# Chargeur_batt.net
KiCad netlist of a schematic drawn in EAGLE
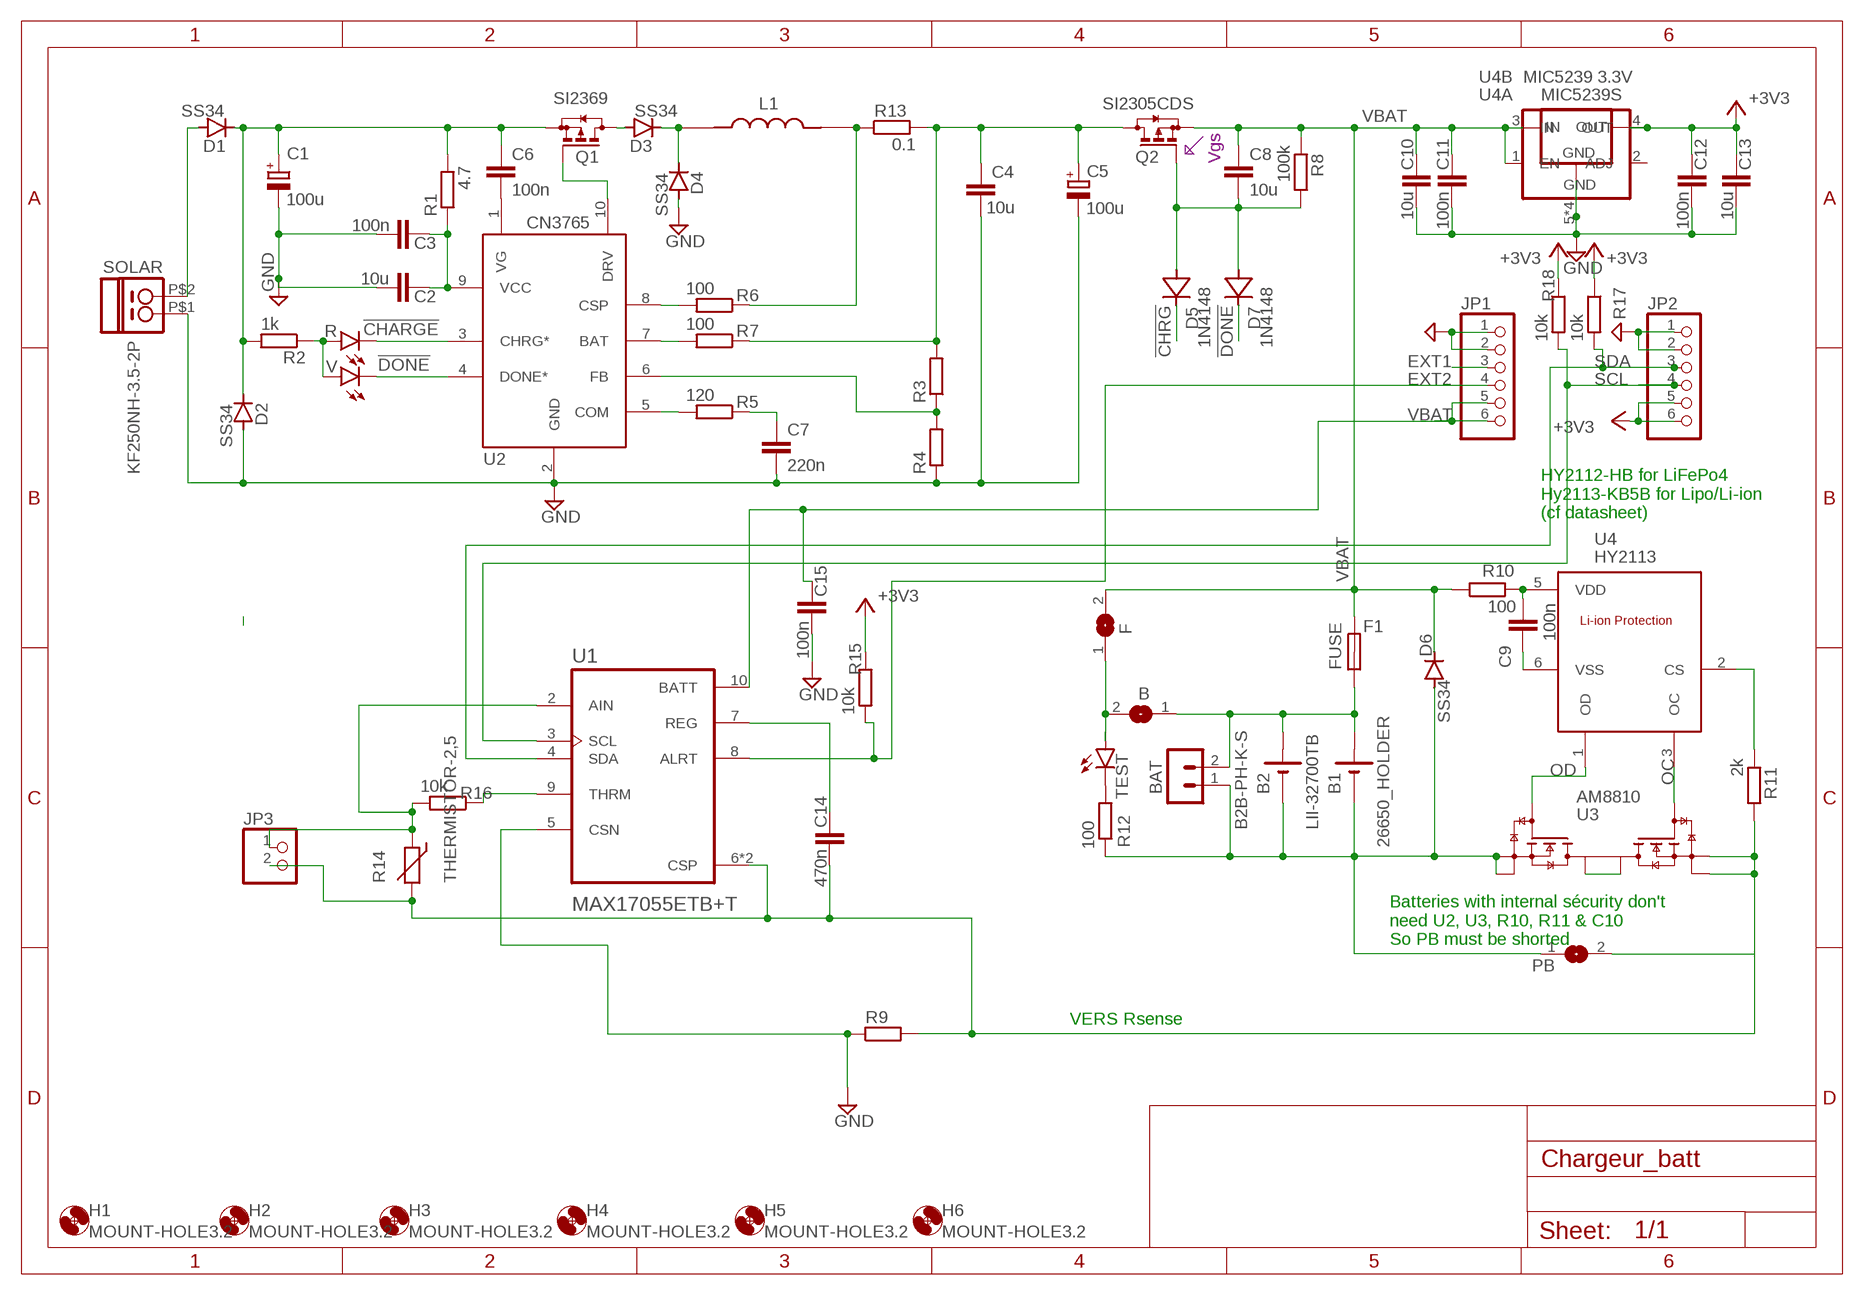
[diagram p0: schematic, sheet 1]

(export (version "E")
  (design (tool "Eeschema 10.0.6"))
  (components
    (comp (ref "B") (value "SJ") (footprint "eagle-import:SJ") (libsource (lib "eagle-import") (part "SJ")))
    (comp (ref "B1")
      (value "26650_HOLDER")
      (footprint "eagle-import:26650")
      (libsource (lib "eagle-import") (part "26650_HOLDER"))
    )
    (comp (ref "B2")
      (value "LII-32700TB")
      (footprint "eagle-import:LII-32700TB")
      (libsource (lib "eagle-import") (part "LII-32700TB"))
    )
    (comp (ref "BAT")
      (value "B2B-PH-K-S")
      (footprint "eagle-import:B2B-PH-K-S")
      (libsource (lib "eagle-import") (part "B2B-PH-K-S"))
    )
    (comp (ref "C1")
      (value "100u")
      (footprint "eagle-import:PANASONIC_D")
      (libsource (lib "eagle-import") (part "CPOL-EUD"))
    )
    (comp (ref "C2")
      (value "10u")
      (footprint "eagle-import:C0805K")
      (libsource (lib "eagle-import") (part "C-EUC0805K"))
    )
    (comp (ref "C3")
      (value "100n")
      (footprint "eagle-import:C0805K")
      (libsource (lib "eagle-import") (part "C-EUC0805K"))
    )
    (comp (ref "C4")
      (value "10u")
      (footprint "eagle-import:C0805K")
      (libsource (lib "eagle-import") (part "C-EUC0805K"))
    )
    (comp (ref "C5")
      (value "100u")
      (footprint "eagle-import:PANASONIC_D")
      (libsource (lib "eagle-import") (part "CPOL-EUD"))
    )
    (comp (ref "C6")
      (value "100n")
      (footprint "eagle-import:C0805K")
      (libsource (lib "eagle-import") (part "C-EUC0805K"))
    )
    (comp (ref "C7")
      (value "220n")
      (footprint "eagle-import:C0805K")
      (libsource (lib "eagle-import") (part "C-EUC0805K"))
    )
    (comp (ref "C8")
      (value "10u")
      (footprint "eagle-import:C0805K")
      (libsource (lib "eagle-import") (part "C-EUC0805K"))
    )
    (comp (ref "C9")
      (value "100n")
      (footprint "eagle-import:C0805K")
      (libsource (lib "eagle-import") (part "C-EUC0805K"))
    )
    (comp (ref "C10")
      (value "10u")
      (footprint "eagle-import:C1206")
      (libsource (lib "eagle-import") (part "CC1206"))
    )
    (comp (ref "C11")
      (value "100n")
      (footprint "eagle-import:C1206")
      (libsource (lib "eagle-import") (part "CC1206"))
    )
    (comp (ref "C12")
      (value "100n")
      (footprint "eagle-import:C1206")
      (libsource (lib "eagle-import") (part "CC1206"))
    )
    (comp (ref "C13")
      (value "10u")
      (footprint "eagle-import:C1206")
      (libsource (lib "eagle-import") (part "CC1206"))
    )
    (comp (ref "C14")
      (value "470n")
      (footprint "eagle-import:C1206")
      (libsource (lib "eagle-import") (part "CC1206"))
    )
    (comp (ref "C15")
      (value "100n")
      (footprint "eagle-import:C0805K")
      (libsource (lib "eagle-import") (part "C-EUC0805K"))
    )
    (comp (ref "D1")
      (value "SS34")
      (footprint "eagle-import:DO-214AC")
      (libsource (lib "eagle-import") (part "DIODE-DO-214AC"))
    )
    (comp (ref "D2")
      (value "SS34")
      (footprint "eagle-import:DO-214AC")
      (libsource (lib "eagle-import") (part "DIODE-DO-214AC"))
    )
    (comp (ref "D3")
      (value "SS34")
      (footprint "eagle-import:DO-214AC")
      (libsource (lib "eagle-import") (part "DIODE-DO-214AC"))
    )
    (comp (ref "D4")
      (value "SS34")
      (footprint "eagle-import:DO-214AC")
      (libsource (lib "eagle-import") (part "DIODE-DO-214AC"))
    )
    (comp (ref "D5")
      (value "1N4148")
      (footprint "eagle-import:VISHAY_1N4148W-E3-08_0")
      (libsource (lib "eagle-import") (part "1N4148"))
    )
    (comp (ref "D6")
      (value "SS34")
      (footprint "eagle-import:DO-214AC")
      (libsource (lib "eagle-import") (part "DIODE-DO-214AC"))
    )
    (comp (ref "D7")
      (value "1N4148")
      (footprint "eagle-import:VISHAY_1N4148W-E3-08_0")
      (libsource (lib "eagle-import") (part "1N4148"))
    )
    (comp (ref "F") (value "SJ") (footprint "eagle-import:SJ") (libsource (lib "eagle-import") (part "SJ")))
    (comp (ref "F1")
      (value "FUSE")
      (footprint "eagle-import:R1206")
      (libsource (lib "eagle-import") (part "FUSE"))
    )
    (comp (ref "H1")
      (value "MOUNT-HOLE3.2")
      (footprint "eagle-import:3,2")
      (libsource (lib "eagle-import") (part "MOUNT-HOLE3.2"))
    )
    (comp (ref "H2")
      (value "MOUNT-HOLE3.2")
      (footprint "eagle-import:3,2")
      (libsource (lib "eagle-import") (part "MOUNT-HOLE3.2"))
    )
    (comp (ref "H3")
      (value "MOUNT-HOLE3.2")
      (footprint "eagle-import:3,2")
      (libsource (lib "eagle-import") (part "MOUNT-HOLE3.2"))
    )
    (comp (ref "H4")
      (value "MOUNT-HOLE3.2")
      (footprint "eagle-import:3,2")
      (libsource (lib "eagle-import") (part "MOUNT-HOLE3.2"))
    )
    (comp (ref "H5")
      (value "MOUNT-HOLE3.2")
      (footprint "eagle-import:3,2")
      (libsource (lib "eagle-import") (part "MOUNT-HOLE3.2"))
    )
    (comp (ref "H6")
      (value "MOUNT-HOLE3.2")
      (footprint "eagle-import:3,2")
      (libsource (lib "eagle-import") (part "MOUNT-HOLE3.2"))
    )
    (comp (ref "JP1")
      (value "PINHD-1X6S")
      (footprint "eagle-import:1X06S")
      (libsource (lib "eagle-import") (part "PINHD-1X6S"))
    )
    (comp (ref "JP2")
      (value "PINHD-1X6S")
      (footprint "eagle-import:1X06S")
      (libsource (lib "eagle-import") (part "PINHD-1X6S"))
    )
    (comp (ref "JP3")
      (value "PINHD-1X2")
      (footprint "eagle-import:1X02")
      (libsource (lib "eagle-import") (part "PINHD-1X2"))
    )
    (comp (ref "L1")
      (value "IND15")
      (footprint "eagle-import:IND_15")
      (libsource (lib "eagle-import") (part "IND15"))
    )
    (comp (ref "PB") (value "SJ") (footprint "eagle-import:SJ") (libsource (lib "eagle-import") (part "SJ")))
    (comp (ref "Q1")
      (value "SI2369")
      (footprint "eagle-import:SOT23")
      (libsource (lib "eagle-import") (part "SI2369"))
    )
    (comp (ref "Q2")
      (value "SI2305CDS")
      (footprint "eagle-import:SOT23")
      (libsource (lib "eagle-import") (part "SI2305CDS"))
    )
    (comp (ref "R")
      (value "LEDSML0805")
      (footprint "eagle-import:SML0805")
      (libsource (lib "eagle-import") (part "LEDSML0805"))
    )
    (comp (ref "R1")
      (value "4.7")
      (footprint "eagle-import:R1206")
      (libsource (lib "eagle-import") (part "R-EU_R1206"))
    )
    (comp (ref "R2")
      (value "1k")
      (footprint "eagle-import:R1206")
      (libsource (lib "eagle-import") (part "R-EU_R1206"))
    )
    (comp (ref "R3")
      (value "R-EU_R1206")
      (footprint "eagle-import:R1206")
      (libsource (lib "eagle-import") (part "R-EU_R1206"))
    )
    (comp (ref "R4")
      (value "R-EU_R1206")
      (footprint "eagle-import:R1206")
      (libsource (lib "eagle-import") (part "R-EU_R1206"))
    )
    (comp (ref "R5")
      (value "120")
      (footprint "eagle-import:R1206")
      (libsource (lib "eagle-import") (part "R-EU_R1206"))
    )
    (comp (ref "R6")
      (value "100")
      (footprint "eagle-import:R1206")
      (libsource (lib "eagle-import") (part "R-EU_R1206"))
    )
    (comp (ref "R7")
      (value "100")
      (footprint "eagle-import:R1206")
      (libsource (lib "eagle-import") (part "R-EU_R1206"))
    )
    (comp (ref "R8")
      (value "100k")
      (footprint "eagle-import:M1206")
      (libsource (lib "eagle-import") (part "resistor_R-EU_M1206"))
    )
    (comp (ref "R9")
      (value "R-EU_R2512")
      (footprint "eagle-import:R2512")
      (libsource (lib "eagle-import") (part "R-EU_R2512"))
    )
    (comp (ref "R10")
      (value "100")
      (footprint "eagle-import:R1206")
      (libsource (lib "eagle-import") (part "R-EU_R1206"))
    )
    (comp (ref "R11")
      (value "2k")
      (footprint "eagle-import:R1206")
      (libsource (lib "eagle-import") (part "resistor_R-EU_R1206"))
    )
    (comp (ref "R12")
      (value "100")
      (footprint "eagle-import:R1206")
      (libsource (lib "eagle-import") (part "R-EU_R1206"))
    )
    (comp (ref "R13")
      (value "0.1")
      (footprint "eagle-import:R2512")
      (libsource (lib "eagle-import") (part "R-EU_R2512"))
    )
    (comp (ref "R14")
      (value "THERMISTOR-2,5")
      (footprint "eagle-import:RS-2,5")
      (libsource (lib "eagle-import") (part "THERMISTOR-2,5"))
    )
    (comp (ref "R15")
      (value "10k")
      (footprint "eagle-import:R1206")
      (libsource (lib "eagle-import") (part "R-EU_R1206"))
    )
    (comp (ref "R16")
      (value "10k")
      (footprint "eagle-import:R1206")
      (libsource (lib "eagle-import") (part "R-EU_R1206"))
    )
    (comp (ref "R17")
      (value "10k")
      (footprint "eagle-import:R1206")
      (libsource (lib "eagle-import") (part "R-EU_R1206"))
    )
    (comp (ref "R18")
      (value "10k")
      (footprint "eagle-import:R1206")
      (libsource (lib "eagle-import") (part "R-EU_R1206"))
    )
    (comp (ref "SOLAR")
      (value "KF250NH-3.5-2P")
      (footprint "eagle-import:KF250NH-3.5-2P")
      (libsource (lib "eagle-import") (part "KF250NH-3.5-2P"))
    )
    (comp (ref "TEST")
      (value "LEDSML0805")
      (footprint "eagle-import:SML0805")
      (libsource (lib "eagle-import") (part "LEDSML0805"))
    )
    (comp (ref "U1")
      (value "MAX17055ETB+T")
      (footprint "eagle-import:SON40P200X250X80-11N")
      (fields (field (name "MF") "Maxim Integrated"))
      (libsource (lib "eagle-import") (part "MAX17055ETB+T"))
    )
    (comp (ref "U2")
      (value "CN3765")
      (footprint "eagle-import:SSOP")
      (libsource (lib "eagle-import") (part "CN3765"))
    )
    (comp (ref "U3")
      (value "AM8810")
      (footprint "eagle-import:TSSOP8")
      (libsource (lib "eagle-import") (part "AM8810"))
    )
    (comp (ref "U4")
      (value "HY2113")
      (footprint "eagle-import:SOT23-6")
      (libsource (lib "eagle-import") (part "HY2113"))
    )
    (comp (ref "U4A")
      (value "MIC5239S")
      (footprint "eagle-import:SOT223")
      (libsource (lib "eagle-import") (part "MIC5239S"))
    )
    (comp (ref "U4B")
      (value "MIC5239 3.3V")
      (footprint "eagle-import:MSOP08")
      (libsource (lib "eagle-import") (part "MIC5239-ADJMM"))
    )
    (comp (ref "V")
      (value "LEDSML0805")
      (footprint "eagle-import:SML0805")
      (libsource (lib "eagle-import") (part "LEDSML0805"))
    )
  )
  (nets
    (net (code "1") (name "+3V3") (class "Default")
      (node (ref "C12") (pin "1") (pinfunction "1_1") (pintype "passive"))
      (node (ref "C13") (pin "1") (pinfunction "1_1") (pintype "passive"))
      (node (ref "JP2") (pin "5") (pinfunction "5_5") (pintype "passive"))
      (node (ref "JP2") (pin "6") (pinfunction "6_6") (pintype "passive"))
      (node (ref "R15") (pin "1") (pinfunction "1_1") (pintype "passive"))
      (node (ref "R17") (pin "1") (pinfunction "1_1") (pintype "passive"))
      (node (ref "R18") (pin "1") (pinfunction "1_1") (pintype "passive"))
      (node (ref "U4A") (pin "3") (pinfunction "OUT_3") (pintype "passive"))
      (node (ref "U4B") (pin "4") (pinfunction "OUT_4") (pintype "passive"))
    )
    (net (code "2") (name "/EXT1") (class "Default")
      (node (ref "JP1") (pin "3") (pinfunction "3_3") (pintype "passive"))
    )
    (net (code "3") (name "/EXT2") (class "Default")
      (node (ref "JP1") (pin "4") (pinfunction "4_4") (pintype "passive"))
      (node (ref "R15") (pin "2") (pinfunction "2_2") (pintype "passive"))
      (node (ref "U1") (pin "8") (pinfunction "ALRT_8") (pintype "output"))
    )
    (net (code "4") (name "/OC") (class "Default")
      (node (ref "U3") (pin "5") (pinfunction "G2_5") (pintype "passive"))
      (node (ref "U4") (pin "3") (pinfunction "OC_3") (pintype "bidirectional"))
    )
    (net (code "5") (name "/OD") (class "Default")
      (node (ref "U3") (pin "4") (pinfunction "G1_4") (pintype "passive"))
      (node (ref "U4") (pin "1") (pinfunction "OD_1") (pintype "bidirectional"))
    )
    (net (code "6") (name "/SCL") (class "Default")
      (node (ref "JP2") (pin "4") (pinfunction "4_4") (pintype "passive"))
      (node (ref "R18") (pin "2") (pinfunction "2_2") (pintype "passive"))
      (node (ref "U1") (pin "3") (pinfunction "SCL_3") (pintype "input"))
    )
    (net (code "7") (name "/SDA") (class "Default")
      (node (ref "JP2") (pin "3") (pinfunction "3_3") (pintype "passive"))
      (node (ref "R17") (pin "2") (pinfunction "2_2") (pintype "passive"))
      (node (ref "U1") (pin "4") (pinfunction "SDA_4") (pintype "input"))
    )
    (net (code "8") (name "/VBAT") (class "Default")
      (node (ref "C10") (pin "1") (pinfunction "1_1") (pintype "passive"))
      (node (ref "C11") (pin "1") (pinfunction "1_1") (pintype "passive"))
      (node (ref "C15") (pin "1") (pinfunction "1_1") (pintype "passive"))
      (node (ref "C8") (pin "1") (pinfunction "1_1") (pintype "passive"))
      (node (ref "D6") (pin "C") (pinfunction "C_C") (pintype "passive"))
      (node (ref "F") (pin "2") (pinfunction "2_2") (pintype "passive"))
      (node (ref "F1") (pin "2") (pinfunction "2_2") (pintype "passive"))
      (node (ref "JP1") (pin "5") (pinfunction "5_5") (pintype "passive"))
      (node (ref "JP1") (pin "6") (pinfunction "6_6") (pintype "passive"))
      (node (ref "Q2") (pin "2") (pinfunction "S_2") (pintype "passive"))
      (node (ref "R10") (pin "1") (pinfunction "1_1") (pintype "passive"))
      (node (ref "R8") (pin "1") (pinfunction "1_1") (pintype "passive"))
      (node (ref "U1") (pin "10") (pinfunction "BATT_10") (pintype "power_in"))
      (node (ref "U4A") (pin "1") (pinfunction "IN_1") (pintype "input"))
      (node (ref "U4B") (pin "1") (pinfunction "EN_1") (pintype "input"))
      (node (ref "U4B") (pin "3") (pinfunction "IN_3") (pintype "input"))
    )
    (net (code "9") (name "/~{CHARGE}") (class "Default")
      (node (ref "R") (pin "C") (pinfunction "C_C") (pintype "passive"))
      (node (ref "U2") (pin "3") (pinfunction "CHRG*_3") (pintype "input"))
    )
    (net (code "10") (name "/~{CHRG}") (class "Default")
      (node (ref "D5") (pin "1") (pinfunction "C_1") (pintype "passive"))
    )
    (net (code "11") (name "/~{DONE}") (class "Default")
      (node (ref "D7") (pin "1") (pinfunction "C_1") (pintype "passive"))
      (node (ref "U2") (pin "4") (pinfunction "DONE*_4") (pintype "input"))
      (node (ref "V") (pin "C") (pinfunction "C_C") (pintype "passive"))
    )
    (net (code "12") (name "GND") (class "Default")
      (node (ref "C1") (pin "-") (pinfunction "-_-") (pintype "passive"))
      (node (ref "C10") (pin "2") (pinfunction "2_2") (pintype "passive"))
      (node (ref "C11") (pin "2") (pinfunction "2_2") (pintype "passive"))
      (node (ref "C12") (pin "2") (pinfunction "2_2") (pintype "passive"))
      (node (ref "C13") (pin "2") (pinfunction "2_2") (pintype "passive"))
      (node (ref "C15") (pin "2") (pinfunction "2_2") (pintype "passive"))
      (node (ref "C2") (pin "2") (pinfunction "2_2") (pintype "passive"))
      (node (ref "C3") (pin "2") (pinfunction "2_2") (pintype "passive"))
      (node (ref "C4") (pin "2") (pinfunction "2_2") (pintype "passive"))
      (node (ref "C5") (pin "-") (pinfunction "-_-") (pintype "passive"))
      (node (ref "C7") (pin "2") (pinfunction "2_2") (pintype "passive"))
      (node (ref "D2") (pin "A") (pinfunction "A_A") (pintype "passive"))
      (node (ref "D4") (pin "A") (pinfunction "A_A") (pintype "passive"))
      (node (ref "JP1") (pin "1") (pinfunction "1_1") (pintype "passive"))
      (node (ref "JP1") (pin "2") (pinfunction "2_2") (pintype "passive"))
      (node (ref "JP2") (pin "1") (pinfunction "1_1") (pintype "passive"))
      (node (ref "JP2") (pin "2") (pinfunction "2_2") (pintype "passive"))
      (node (ref "R4") (pin "1") (pinfunction "1_1") (pintype "passive"))
      (node (ref "R9") (pin "1") (pinfunction "1_1") (pintype "passive"))
      (node (ref "SOLAR") (pin "P$1") (pinfunction "1_P$1") (pintype "passive"))
      (node (ref "U1") (pin "5") (pinfunction "CSN_5") (pintype "bidirectional"))
      (node (ref "U2") (pin "2") (pinfunction "GND_2") (pintype "power_in"))
      (node (ref "U4A") (pin "2") (pinfunction "GND_2") (pintype "passive"))
      (node (ref "U4A") (pin "4") (pinfunction "GND_4") (pintype "passive"))
      (node (ref "U4B") (pin "5") (pinfunction "GND_5") (pintype "power_in"))
      (node (ref "U4B") (pin "6") (pinfunction "GND_6") (pintype "power_in"))
      (node (ref "U4B") (pin "7") (pinfunction "GND_7") (pintype "power_in"))
      (node (ref "U4B") (pin "8") (pinfunction "GND_8") (pintype "power_in"))
    )
    (net (code "13") (name "Net-(B-Pad1)") (class "Default")
      (node (ref "B") (pin "1") (pinfunction "1_1") (pintype "passive"))
      (node (ref "B1") (pin "+") (pinfunction "+_+") (pintype "passive"))
      (node (ref "B2") (pin "+") (pinfunction "+_+") (pintype "passive"))
      (node (ref "BAT") (pin "2") (pinfunction "2_2") (pintype "passive"))
      (node (ref "F1") (pin "1") (pinfunction "1_1") (pintype "passive"))
    )
    (net (code "14") (name "Net-(B-Pad2)") (class "Default")
      (node (ref "B") (pin "2") (pinfunction "2_2") (pintype "passive"))
      (node (ref "F") (pin "1") (pinfunction "1_1") (pintype "passive"))
      (node (ref "TEST") (pin "A") (pinfunction "A_A") (pintype "passive"))
    )
    (net (code "15") (name "Net-(C7-Pad1)") (class "Default")
      (node (ref "C7") (pin "1") (pinfunction "1_1") (pintype "passive"))
      (node (ref "R5") (pin "1") (pinfunction "1_1") (pintype "passive"))
    )
    (net (code "16") (name "Net-(D3-PadC)") (class "Default")
      (node (ref "D3") (pin "C") (pinfunction "C_C") (pintype "passive"))
      (node (ref "D4") (pin "C") (pinfunction "C_C") (pintype "passive"))
      (node (ref "L1") (pin "1") (pinfunction "1_1") (pintype "passive"))
    )
    (net (code "17") (name "Net-(D5-A)") (class "Default")
      (node (ref "C8") (pin "2") (pinfunction "2_2") (pintype "passive"))
      (node (ref "D5") (pin "2") (pinfunction "A_2") (pintype "passive"))
      (node (ref "D7") (pin "2") (pinfunction "A_2") (pintype "passive"))
      (node (ref "Q2") (pin "1") (pinfunction "G_1") (pintype "passive"))
      (node (ref "R8") (pin "2") (pinfunction "2_2") (pintype "passive"))
    )
    (net (code "18") (name "Net-(L1-Pad2)") (class "Default")
      (node (ref "L1") (pin "2") (pinfunction "2_2") (pintype "passive"))
      (node (ref "R13") (pin "1") (pinfunction "1_1") (pintype "passive"))
      (node (ref "R6") (pin "1") (pinfunction "1_1") (pintype "passive"))
    )
    (net (code "19") (name "Net-(Q1-D)") (class "Default")
      (node (ref "D3") (pin "A") (pinfunction "A_A") (pintype "passive"))
      (node (ref "Q1") (pin "3") (pinfunction "D_3") (pintype "passive"))
    )
    (net (code "20") (name "Net-(Q1-G)") (class "Default")
      (node (ref "Q1") (pin "1") (pinfunction "G_1") (pintype "passive"))
      (node (ref "U2") (pin "10") (pinfunction "DRV_10") (pintype "bidirectional"))
    )
    (net (code "21") (name "Net-(Q1-S)") (class "Default")
      (node (ref "C1") (pin "+") (pinfunction "+_+") (pintype "passive"))
      (node (ref "C6") (pin "1") (pinfunction "1_1") (pintype "passive"))
      (node (ref "D1") (pin "C") (pinfunction "C_C") (pintype "passive"))
      (node (ref "D2") (pin "C") (pinfunction "C_C") (pintype "passive"))
      (node (ref "Q1") (pin "2") (pinfunction "S_2") (pintype "passive"))
      (node (ref "R1") (pin "2") (pinfunction "2_2") (pintype "passive"))
      (node (ref "R2") (pin "2") (pinfunction "2_2") (pintype "passive"))
    )
    (net (code "22") (name "Net-(Q2-D)") (class "Default")
      (node (ref "C4") (pin "1") (pinfunction "1_1") (pintype "passive"))
      (node (ref "C5") (pin "+") (pinfunction "+_+") (pintype "passive"))
      (node (ref "Q2") (pin "3") (pinfunction "D_3") (pintype "passive"))
      (node (ref "R13") (pin "2") (pinfunction "2_2") (pintype "passive"))
      (node (ref "R3") (pin "2") (pinfunction "2_2") (pintype "passive"))
      (node (ref "R7") (pin "1") (pinfunction "1_1") (pintype "passive"))
    )
    (net (code "23") (name "Net-(R-PadA)") (class "Default")
      (node (ref "R") (pin "A") (pinfunction "A_A") (pintype "passive"))
      (node (ref "R2") (pin "1") (pinfunction "1_1") (pintype "passive"))
      (node (ref "V") (pin "A") (pinfunction "A_A") (pintype "passive"))
    )
    (net (code "24") (name "Net-(R12-Pad1)") (class "Default")
      (node (ref "R12") (pin "1") (pinfunction "1_1") (pintype "passive"))
      (node (ref "TEST") (pin "C") (pinfunction "C_C") (pintype "passive"))
    )
    (net (code "25") (name "Net-(SOLAR-2)") (class "Default")
      (node (ref "D1") (pin "A") (pinfunction "A_A") (pintype "passive"))
      (node (ref "SOLAR") (pin "P$2") (pinfunction "2_P$2") (pintype "passive"))
    )
    (net (code "26") (name "Net-(U1-AIN)") (class "Default")
      (node (ref "JP3") (pin "1") (pinfunction "1_1") (pintype "passive"))
      (node (ref "R14") (pin "1") (pinfunction "1_1") (pintype "passive"))
      (node (ref "R16") (pin "2") (pinfunction "2_2") (pintype "passive"))
      (node (ref "U1") (pin "2") (pinfunction "AIN_2") (pintype "input"))
    )
    (net (code "27") (name "Net-(U1-REG)") (class "Default")
      (node (ref "C14") (pin "1") (pinfunction "1_1") (pintype "passive"))
      (node (ref "U1") (pin "7") (pinfunction "REG_7") (pintype "output"))
    )
    (net (code "28") (name "Net-(U1-THRM)") (class "Default")
      (node (ref "R16") (pin "1") (pinfunction "1_1") (pintype "passive"))
      (node (ref "U1") (pin "9") (pinfunction "THRM_9") (pintype "input"))
    )
    (net (code "29") (name "Net-(U2-BAT)") (class "Default")
      (node (ref "R7") (pin "2") (pinfunction "2_2") (pintype "passive"))
      (node (ref "U2") (pin "7") (pinfunction "BAT_7") (pintype "bidirectional"))
    )
    (net (code "30") (name "Net-(U2-COM)") (class "Default")
      (node (ref "R5") (pin "2") (pinfunction "2_2") (pintype "passive"))
      (node (ref "U2") (pin "5") (pinfunction "COM_5") (pintype "input"))
    )
    (net (code "31") (name "Net-(U2-CSP)") (class "Default")
      (node (ref "R6") (pin "2") (pinfunction "2_2") (pintype "passive"))
      (node (ref "U2") (pin "8") (pinfunction "CSP_8") (pintype "bidirectional"))
    )
    (net (code "32") (name "Net-(U2-FB)") (class "Default")
      (node (ref "R3") (pin "1") (pinfunction "1_1") (pintype "passive"))
      (node (ref "R4") (pin "2") (pinfunction "2_2") (pintype "passive"))
      (node (ref "U2") (pin "6") (pinfunction "FB_6") (pintype "input"))
    )
    (net (code "33") (name "Net-(U2-VCC)") (class "Default")
      (node (ref "C2") (pin "1") (pinfunction "1_1") (pintype "passive"))
      (node (ref "C3") (pin "1") (pinfunction "1_1") (pintype "passive"))
      (node (ref "R1") (pin "1") (pinfunction "1_1") (pintype "passive"))
      (node (ref "U2") (pin "9") (pinfunction "VCC_9") (pintype "power_in"))
    )
    (net (code "34") (name "Net-(U2-VG)") (class "Default")
      (node (ref "C6") (pin "2") (pinfunction "2_2") (pintype "passive"))
      (node (ref "U2") (pin "1") (pinfunction "VG_1") (pintype "bidirectional"))
    )
    (net (code "35") (name "Net-(U3-D1)") (class "Default")
      (node (ref "U3") (pin "1") (pinfunction "D1_1") (pintype "passive"))
      (node (ref "U3") (pin "8") (pinfunction "D2_8") (pintype "passive"))
    )
    (net (code "36") (name "Net-(U3-S1)") (class "Default")
      (node (ref "B1") (pin "-") (pinfunction "-_-") (pintype "passive"))
      (node (ref "B2") (pin "-") (pinfunction "-_-") (pintype "passive"))
      (node (ref "BAT") (pin "1") (pinfunction "1_1") (pintype "passive"))
      (node (ref "D6") (pin "A") (pinfunction "A_A") (pintype "passive"))
      (node (ref "PB") (pin "1") (pinfunction "1_1") (pintype "passive"))
      (node (ref "R12") (pin "2") (pinfunction "2_2") (pintype "passive"))
      (node (ref "U3") (pin "2") (pinfunction "S1_2") (pintype "passive"))
      (node (ref "U3") (pin "3") (pinfunction "S1A_3") (pintype "passive"))
    )
    (net (code "37") (name "Net-(U3-S2)") (class "Default")
      (node (ref "C14") (pin "2") (pinfunction "2_2") (pintype "passive"))
      (node (ref "JP3") (pin "2") (pinfunction "2_2") (pintype "passive"))
      (node (ref "PB") (pin "2") (pinfunction "2_2") (pintype "passive"))
      (node (ref "R11") (pin "2") (pinfunction "2_2") (pintype "passive"))
      (node (ref "R14") (pin "2") (pinfunction "2_2") (pintype "passive"))
      (node (ref "R9") (pin "2") (pinfunction "2_2") (pintype "passive"))
      (node (ref "U1") (pin "11") (pinfunction "CSP_11") (pintype "power_in"))
      (node (ref "U1") (pin "6") (pinfunction "CSP_6") (pintype "power_in"))
      (node (ref "U3") (pin "6") (pinfunction "S2_6") (pintype "passive"))
      (node (ref "U3") (pin "7") (pinfunction "S2A_7") (pintype "passive"))
    )
    (net (code "38") (name "Net-(U4-CS)") (class "Default")
      (node (ref "R11") (pin "1") (pinfunction "1_1") (pintype "passive"))
      (node (ref "U4") (pin "2") (pinfunction "CS_2") (pintype "bidirectional"))
    )
    (net (code "39") (name "Net-(U4-VDD)") (class "Default")
      (node (ref "C9") (pin "1") (pinfunction "1_1") (pintype "passive"))
      (node (ref "R10") (pin "2") (pinfunction "2_2") (pintype "passive"))
      (node (ref "U4") (pin "5") (pinfunction "VDD_5") (pintype "power_in"))
    )
    (net (code "40") (name "Net-(U4-VSS)") (class "Default")
      (node (ref "C9") (pin "2") (pinfunction "2_2") (pintype "passive"))
      (node (ref "U4") (pin "6") (pinfunction "VSS_6") (pintype "power_in"))
    )
    (net (code "41") (name "unconnected-(U4B-ADJ-Pad2)") (class "Default")
      (node (ref "U4B") (pin "2") (pinfunction "ADJ_2") (pintype "passive"))
    )
  )
)
